# Reciever_Reed.net
KiCad netlist of a schematic drawn in EAGLE
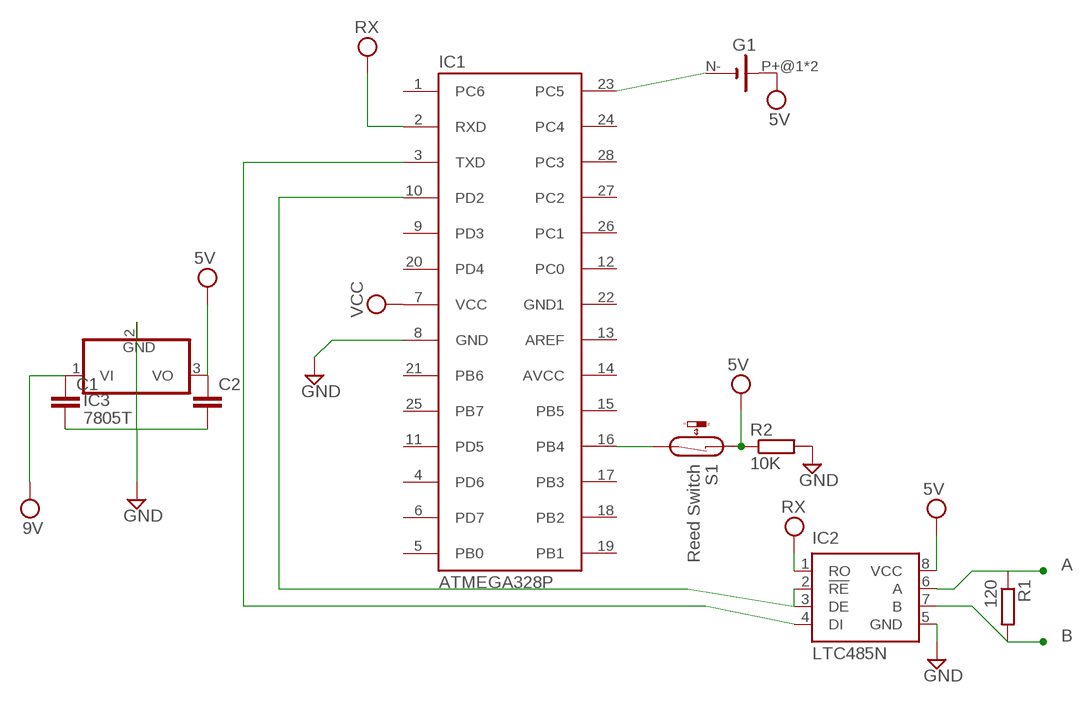
[diagram p0: schematic, sheet 1]

(export (version "E")
  (design (tool "Eeschema 10.0.6"))
  (components
    (comp (ref "C1")
      (value "C-EU050-030X075")
      (footprint "eagle-import:C050-030X075")
      (libsource (lib "eagle-import") (part "C-EU050-030X075"))
    )
    (comp (ref "C2")
      (value "C-EU050-030X075")
      (footprint "eagle-import:C050-030X075")
      (libsource (lib "eagle-import") (part "C-EU050-030X075"))
    )
    (comp (ref "G1")
      (value "BATTERY-HOLDER_11.6MM")
      (footprint "eagle-import:CELL_RETAINER_11.6MM")
      (fields (field (name "MF") "KEYSTONE") (field (name "MPN") "2997"))
      (libsource (lib "eagle-import") (part "BATTERY-HOLDER_11.6MM"))
    )
    (comp (ref "IC1")
      (value "ATMEGA328P")
      (footprint "eagle-import:DIL28-3")
      (libsource (lib "eagle-import") (part "ATMEGA328P"))
    )
    (comp (ref "IC2")
      (value "LTC485N")
      (footprint "eagle-import:DIL08")
      (libsource (lib "eagle-import") (part "LTC485N"))
    )
    (comp (ref "IC3")
      (value "7805T")
      (footprint "eagle-import:TO220H")
      (libsource (lib "eagle-import") (part "78T05"))
    )
    (comp (ref "R1")
      (value "120")
      (footprint "eagle-import:R0805")
      (libsource (lib "eagle-import") (part "R"))
    )
    (comp (ref "R2")
      (value "10K")
      (footprint "eagle-import:R0805")
      (libsource (lib "eagle-import") (part "R"))
    )
    (comp (ref "S1")
      (value "Reed Switch")
      (footprint "eagle-import:CT10-G1")
      (fields (field (name "MF") "COTO TECHNOLOGY") (field (name "MPN") "CT10-1530-G1"))
      (libsource (lib "eagle-import") (part "REED-SWITCH-CT10-1530-G1"))
    )
  )
  (nets
    (net (code "1") (name "/A") (class "Default")
      (node (ref "IC2") (pin "6") (pinfunction "A_6") (pintype "bidirectional"))
      (node (ref "R1") (pin "1") (pinfunction "1_1") (pintype "passive"))
    )
    (net (code "2") (name "/B") (class "Default")
      (node (ref "IC2") (pin "7") (pinfunction "B_7") (pintype "bidirectional"))
      (node (ref "R1") (pin "2") (pinfunction "2_2") (pintype "passive"))
    )
    (net (code "3") (name "/GND1") (class "Default")
      (node (ref "IC1") (pin "22") (pinfunction "GND1_22") (pintype "power_in"))
    )
    (net (code "4") (name "5V") (class "Default")
      (node (ref "C1") (pin "1") (pinfunction "1_1") (pintype "passive"))
      (node (ref "C2") (pin "1") (pinfunction "1_1") (pintype "passive"))
      (node (ref "G1") (pin "P+@1") (pinfunction "+_P+@1") (pintype "passive"))
      (node (ref "G1") (pin "P+@2") (pinfunction "+_P+@2") (pintype "passive"))
      (node (ref "IC1") (pin "2") (pinfunction "RXD_2") (pintype "bidirectional"))
      (node (ref "IC1") (pin "7") (pinfunction "VCC_7") (pintype "power_in"))
      (node (ref "IC2") (pin "1") (pinfunction "RO_1") (pintype "output"))
      (node (ref "IC2") (pin "8") (pinfunction "VCC_8") (pintype "input"))
      (node (ref "IC3") (pin "1") (pinfunction "VI_1") (pintype "input"))
      (node (ref "IC3") (pin "3") (pinfunction "VO_3") (pintype "passive"))
      (node (ref "R2") (pin "1") (pinfunction "1_1") (pintype "passive"))
      (node (ref "S1") (pin "1") (pinfunction "1_1") (pintype "passive"))
    )
    (net (code "5") (name "GND") (class "Default")
      (node (ref "C1") (pin "2") (pinfunction "2_2") (pintype "passive"))
      (node (ref "C2") (pin "2") (pinfunction "2_2") (pintype "passive"))
      (node (ref "IC1") (pin "8") (pinfunction "GND_8") (pintype "power_in"))
      (node (ref "IC2") (pin "5") (pinfunction "GND_5") (pintype "input"))
      (node (ref "IC3") (pin "2") (pinfunction "GND_2") (pintype "passive"))
      (node (ref "R2") (pin "2") (pinfunction "2_2") (pintype "passive"))
    )
    (net (code "6") (name "Net-(G1--)") (class "Default")
      (node (ref "G1") (pin "N-") (pinfunction "-_N-") (pintype "passive"))
      (node (ref "IC1") (pin "23") (pinfunction "PC5_23") (pintype "bidirectional"))
    )
    (net (code "7") (name "Net-(IC1-PB4)") (class "Default")
      (node (ref "IC1") (pin "16") (pinfunction "PB4_16") (pintype "bidirectional"))
      (node (ref "S1") (pin "2") (pinfunction "2_2") (pintype "passive"))
    )
    (net (code "8") (name "Net-(IC1-PD2)") (class "Default")
      (node (ref "IC1") (pin "10") (pinfunction "PD2_10") (pintype "bidirectional"))
      (node (ref "IC2") (pin "2") (pinfunction "~{RE}_2") (pintype "input"))
      (node (ref "IC2") (pin "3") (pinfunction "DE_3") (pintype "input"))
    )
    (net (code "9") (name "Net-(IC1-TXD)") (class "Default")
      (node (ref "IC1") (pin "3") (pinfunction "TXD_3") (pintype "bidirectional"))
      (node (ref "IC2") (pin "4") (pinfunction "DI_4") (pintype "input"))
    )
    (net (code "10") (name "unconnected-(IC1-AREF-Pad13)") (class "Default")
      (node (ref "IC1") (pin "13") (pinfunction "AREF_13") (pintype "bidirectional"))
    )
    (net (code "11") (name "unconnected-(IC1-AVCC-Pad14)") (class "Default")
      (node (ref "IC1") (pin "14") (pinfunction "AVCC_14") (pintype "bidirectional"))
    )
    (net (code "12") (name "unconnected-(IC1-PB0-Pad5)") (class "Default")
      (node (ref "IC1") (pin "5") (pinfunction "PB0_5") (pintype "bidirectional"))
    )
    (net (code "13") (name "unconnected-(IC1-PB1-Pad19)") (class "Default")
      (node (ref "IC1") (pin "19") (pinfunction "PB1_19") (pintype "bidirectional"))
    )
    (net (code "14") (name "unconnected-(IC1-PB2-Pad18)") (class "Default")
      (node (ref "IC1") (pin "18") (pinfunction "PB2_18") (pintype "bidirectional"))
    )
    (net (code "15") (name "unconnected-(IC1-PB3-Pad17)") (class "Default")
      (node (ref "IC1") (pin "17") (pinfunction "PB3_17") (pintype "bidirectional"))
    )
    (net (code "16") (name "unconnected-(IC1-PB5-Pad15)") (class "Default")
      (node (ref "IC1") (pin "15") (pinfunction "PB5_15") (pintype "bidirectional"))
    )
    (net (code "17") (name "unconnected-(IC1-PB6-Pad21)") (class "Default")
      (node (ref "IC1") (pin "21") (pinfunction "PB6_21") (pintype "passive"))
    )
    (net (code "18") (name "unconnected-(IC1-PB7-Pad25)") (class "Default")
      (node (ref "IC1") (pin "25") (pinfunction "PB7_25") (pintype "bidirectional"))
    )
    (net (code "19") (name "unconnected-(IC1-PC0-Pad12)") (class "Default")
      (node (ref "IC1") (pin "12") (pinfunction "PC0_12") (pintype "bidirectional"))
    )
    (net (code "20") (name "unconnected-(IC1-PC1-Pad26)") (class "Default")
      (node (ref "IC1") (pin "26") (pinfunction "PC1_26") (pintype "bidirectional"))
    )
    (net (code "21") (name "unconnected-(IC1-PC2-Pad27)") (class "Default")
      (node (ref "IC1") (pin "27") (pinfunction "PC2_27") (pintype "bidirectional"))
    )
    (net (code "22") (name "unconnected-(IC1-PC3-Pad28)") (class "Default")
      (node (ref "IC1") (pin "28") (pinfunction "PC3_28") (pintype "bidirectional"))
    )
    (net (code "23") (name "unconnected-(IC1-PC4-Pad24)") (class "Default")
      (node (ref "IC1") (pin "24") (pinfunction "PC4_24") (pintype "bidirectional"))
    )
    (net (code "24") (name "unconnected-(IC1-PC6-Pad1)") (class "Default")
      (node (ref "IC1") (pin "1") (pinfunction "PC6_1") (pintype "bidirectional"))
    )
    (net (code "25") (name "unconnected-(IC1-PD3-Pad9)") (class "Default")
      (node (ref "IC1") (pin "9") (pinfunction "PD3_9") (pintype "bidirectional"))
    )
    (net (code "26") (name "unconnected-(IC1-PD4-Pad20)") (class "Default")
      (node (ref "IC1") (pin "20") (pinfunction "PD4_20") (pintype "passive"))
    )
    (net (code "27") (name "unconnected-(IC1-PD5-Pad11)") (class "Default")
      (node (ref "IC1") (pin "11") (pinfunction "PD5_11") (pintype "bidirectional"))
    )
    (net (code "28") (name "unconnected-(IC1-PD6-Pad4)") (class "Default")
      (node (ref "IC1") (pin "4") (pinfunction "PD6_4") (pintype "bidirectional"))
    )
    (net (code "29") (name "unconnected-(IC1-PD7-Pad6)") (class "Default")
      (node (ref "IC1") (pin "6") (pinfunction "PD7_6") (pintype "bidirectional"))
    )
  )
)
